# SoC_MII.net
KiCad netlist of a schematic drawn in Altium Designer
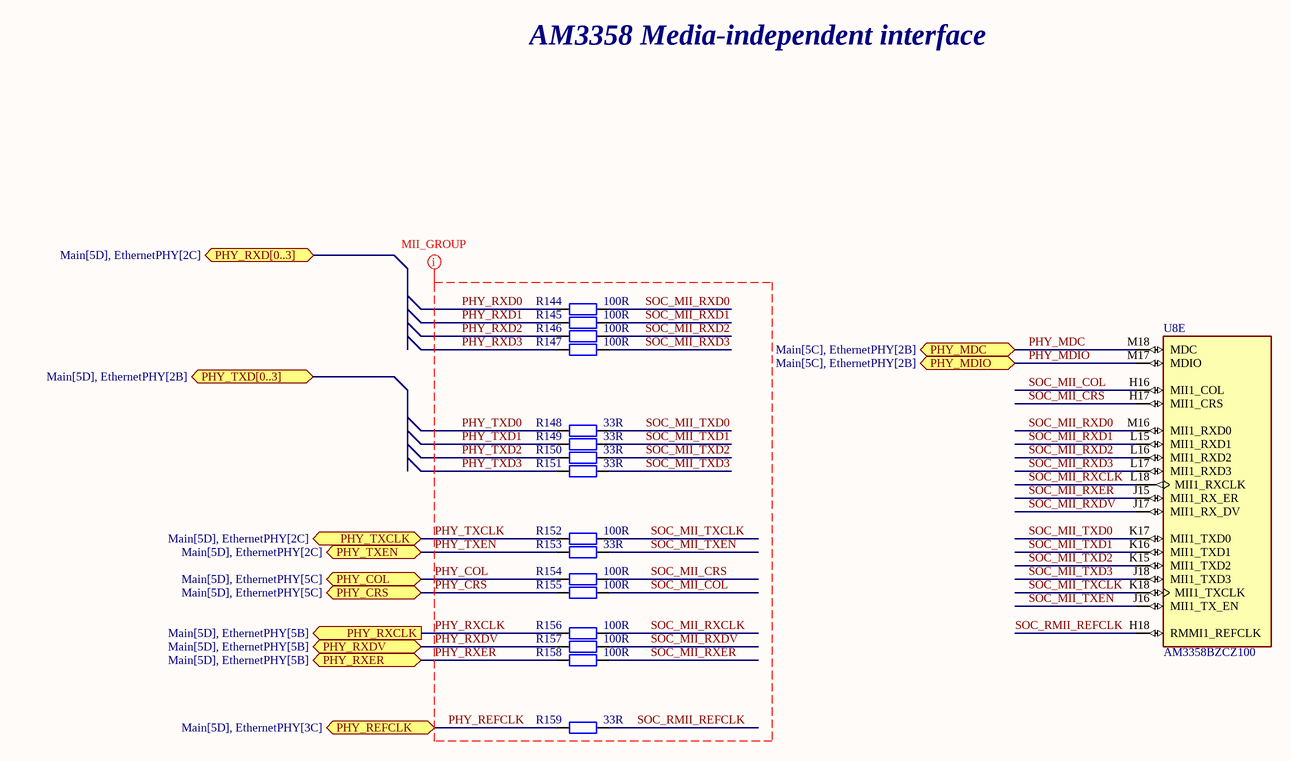
[diagram p0: SoC_MII.SchDoc]

(export (version "E")
  (design (tool "Eeschema 10.0.6"))
  (components
    (comp (ref "R144")
      (value "100R")
      (footprint "R_0402")
      (description "Resistor 0402 SMD")
      (libsource (lib "tor1kkLib") (part "R_0402"))
    )
    (comp (ref "R145")
      (value "100R")
      (footprint "R_0402")
      (description "Resistor 0402 SMD")
      (libsource (lib "tor1kkLib") (part "R_0402"))
    )
    (comp (ref "R146")
      (value "100R")
      (footprint "R_0402")
      (description "Resistor 0402 SMD")
      (libsource (lib "tor1kkLib") (part "R_0402"))
    )
    (comp (ref "R147")
      (value "100R")
      (footprint "R_0402")
      (description "Resistor 0402 SMD")
      (libsource (lib "tor1kkLib") (part "R_0402"))
    )
    (comp (ref "R148")
      (value "33R")
      (footprint "R_0402")
      (description "Resistor 0402 SMD")
      (libsource (lib "tor1kkLib") (part "R_0402"))
    )
    (comp (ref "R149")
      (value "33R")
      (footprint "R_0402")
      (description "Resistor 0402 SMD")
      (libsource (lib "tor1kkLib") (part "R_0402"))
    )
    (comp (ref "R150")
      (value "33R")
      (footprint "R_0402")
      (description "Resistor 0402 SMD")
      (libsource (lib "tor1kkLib") (part "R_0402"))
    )
    (comp (ref "R151")
      (value "33R")
      (footprint "R_0402")
      (description "Resistor 0402 SMD")
      (libsource (lib "tor1kkLib") (part "R_0402"))
    )
    (comp (ref "R152")
      (value "100R")
      (footprint "R_0402")
      (description "Resistor 0402 SMD")
      (libsource (lib "tor1kkLib") (part "R_0402"))
    )
    (comp (ref "R153")
      (value "33R")
      (footprint "R_0402")
      (description "Resistor 0402 SMD")
      (libsource (lib "tor1kkLib") (part "R_0402"))
    )
    (comp (ref "R154")
      (value "100R")
      (footprint "R_0402")
      (description "Resistor 0402 SMD")
      (libsource (lib "tor1kkLib") (part "R_0402"))
    )
    (comp (ref "R155")
      (value "100R")
      (footprint "R_0402")
      (description "Resistor 0402 SMD")
      (libsource (lib "tor1kkLib") (part "R_0402"))
    )
    (comp (ref "R156")
      (value "100R")
      (footprint "R_0402")
      (description "Resistor 0402 SMD")
      (libsource (lib "tor1kkLib") (part "R_0402"))
    )
    (comp (ref "R157")
      (value "100R")
      (footprint "R_0402")
      (description "Resistor 0402 SMD")
      (libsource (lib "tor1kkLib") (part "R_0402"))
    )
    (comp (ref "R158")
      (value "100R")
      (footprint "R_0402")
      (description "Resistor 0402 SMD")
      (libsource (lib "tor1kkLib") (part "R_0402"))
    )
    (comp (ref "R159")
      (value "33R")
      (footprint "R_0402")
      (description "Resistor 0402 SMD")
      (libsource (lib "tor1kkLib") (part "R_0402"))
    )
    (comp (ref "U8")
      (value "AM3358BZCZ100")
      (footprint "BGA324C80P18X18_1500X1500X140")
      (description "ARM-ASeries 1GHz NFBGA-324 Microcontrollers (MCU/MPU/SOC) ROHS")
      (fields (field (name "MANUFACTURER") "Texas Instruments"))
      (libsource (lib "tor1kkLib") (part "AM3358BZCZ100"))
    )
  )
  (nets
    (net (code "1") (name "/PHY_COL") (class "Default") (node (ref "R154") (pin "1") (pintype "passive")))
    (net (code "2") (name "/PHY_CRS") (class "Default") (node (ref "R155") (pin "1") (pintype "passive")))
    (net (code "3") (name "/PHY_MDC") (class "Default")
      (node (ref "U8") (pin "M18") (pinfunction "MDC_M18") (pintype "bidirectional"))
    )
    (net (code "4") (name "/PHY_MDIO") (class "Default")
      (node (ref "U8") (pin "M17") (pinfunction "MDIO_M17") (pintype "bidirectional"))
    )
    (net (code "5") (name "/PHY_REFCLK") (class "Default") (node (ref "R159") (pin "1") (pintype "passive")))
    (net (code "6") (name "/PHY_RXCLK") (class "Default") (node (ref "R156") (pin "1") (pintype "passive")))
    (net (code "7") (name "/PHY_RXD0") (class "Default") (node (ref "R144") (pin "1") (pintype "passive")))
    (net (code "8") (name "/PHY_RXD1") (class "Default") (node (ref "R145") (pin "1") (pintype "passive")))
    (net (code "9") (name "/PHY_RXD2") (class "Default") (node (ref "R146") (pin "1") (pintype "passive")))
    (net (code "10") (name "/PHY_RXD3") (class "Default") (node (ref "R147") (pin "1") (pintype "passive")))
    (net (code "11") (name "/PHY_RXDV") (class "Default") (node (ref "R157") (pin "1") (pintype "passive")))
    (net (code "13") (name "/PHY_RXER") (class "Default") (node (ref "R158") (pin "1") (pintype "passive")))
    (net (code "14") (name "/PHY_TXCLK") (class "Default") (node (ref "R152") (pin "1") (pintype "passive")))
    (net (code "15") (name "/PHY_TXD0") (class "Default") (node (ref "R148") (pin "1") (pintype "passive")))
    (net (code "16") (name "/PHY_TXD1") (class "Default") (node (ref "R149") (pin "1") (pintype "passive")))
    (net (code "17") (name "/PHY_TXD2") (class "Default") (node (ref "R150") (pin "1") (pintype "passive")))
    (net (code "18") (name "/PHY_TXD3") (class "Default") (node (ref "R151") (pin "1") (pintype "passive")))
    (net (code "20") (name "/PHY_TXEN") (class "Default") (node (ref "R153") (pin "1") (pintype "passive")))
    (net (code "21") (name "/SOC_MII_COL") (class "Default")
      (node (ref "R155") (pin "2") (pintype "passive"))
      (node (ref "U8") (pin "H16") (pinfunction "MII1_COL_H16") (pintype "bidirectional"))
    )
    (net (code "22") (name "/SOC_MII_CRS") (class "Default")
      (node (ref "R154") (pin "2") (pintype "passive"))
      (node (ref "U8") (pin "H17") (pinfunction "MII1_CRS_H17") (pintype "bidirectional"))
    )
    (net (code "23") (name "/SOC_MII_RXCLK") (class "Default")
      (node (ref "R156") (pin "2") (pintype "passive"))
      (node (ref "U8") (pin "L18") (pinfunction "MII1_RXCLK_L18") (pintype "output"))
    )
    (net (code "24") (name "/SOC_MII_RXD0") (class "Default")
      (node (ref "R144") (pin "2") (pintype "passive"))
      (node (ref "U8") (pin "M16") (pinfunction "MII1_RXD0_M16") (pintype "bidirectional"))
    )
    (net (code "25") (name "/SOC_MII_RXD1") (class "Default")
      (node (ref "R145") (pin "2") (pintype "passive"))
      (node (ref "U8") (pin "L15") (pinfunction "MII1_RXD1_L15") (pintype "bidirectional"))
    )
    (net (code "26") (name "/SOC_MII_RXD2") (class "Default")
      (node (ref "R146") (pin "2") (pintype "passive"))
      (node (ref "U8") (pin "L16") (pinfunction "MII1_RXD2_L16") (pintype "bidirectional"))
    )
    (net (code "27") (name "/SOC_MII_RXD3") (class "Default")
      (node (ref "R147") (pin "2") (pintype "passive"))
      (node (ref "U8") (pin "L17") (pinfunction "MII1_RXD3_L17") (pintype "bidirectional"))
    )
    (net (code "28") (name "/SOC_MII_RXDV") (class "Default")
      (node (ref "R157") (pin "2") (pintype "passive"))
      (node (ref "U8") (pin "J17") (pinfunction "MII1_RX_DV_J17") (pintype "bidirectional"))
    )
    (net (code "29") (name "/SOC_MII_RXER") (class "Default")
      (node (ref "R158") (pin "2") (pintype "passive"))
      (node (ref "U8") (pin "J15") (pinfunction "MII1_RX_ER_J15") (pintype "bidirectional"))
    )
    (net (code "30") (name "/SOC_MII_TXCLK") (class "Default")
      (node (ref "R152") (pin "2") (pintype "passive"))
      (node (ref "U8") (pin "K18") (pinfunction "MII1_TXCLK_K18") (pintype "bidirectional"))
    )
    (net (code "31") (name "/SOC_MII_TXD0") (class "Default")
      (node (ref "R148") (pin "2") (pintype "passive"))
      (node (ref "U8") (pin "K17") (pinfunction "MII1_TXD0_K17") (pintype "bidirectional"))
    )
    (net (code "32") (name "/SOC_MII_TXD1") (class "Default")
      (node (ref "R149") (pin "2") (pintype "passive"))
      (node (ref "U8") (pin "K16") (pinfunction "MII1_TXD1_K16") (pintype "bidirectional"))
    )
    (net (code "33") (name "/SOC_MII_TXD2") (class "Default")
      (node (ref "R150") (pin "2") (pintype "passive"))
      (node (ref "U8") (pin "K15") (pinfunction "MII1_TXD2_K15") (pintype "bidirectional"))
    )
    (net (code "34") (name "/SOC_MII_TXD3") (class "Default")
      (node (ref "R151") (pin "2") (pintype "passive"))
      (node (ref "U8") (pin "J18") (pinfunction "MII1_TXD3_J18") (pintype "bidirectional"))
    )
    (net (code "35") (name "/SOC_MII_TXEN") (class "Default")
      (node (ref "R153") (pin "2") (pintype "passive"))
      (node (ref "U8") (pin "J16") (pinfunction "MII1_TX_EN_J16") (pintype "bidirectional"))
    )
    (net (code "36") (name "/SOC_RMII_REFCLK") (class "Default")
      (node (ref "R159") (pin "2") (pintype "passive"))
      (node (ref "U8") (pin "H18") (pinfunction "RMMI1_REFCLK_H18") (pintype "bidirectional"))
    )
  )
)
